# full_motor_1.net
KiCad netlist of a schematic drawn in EAGLE
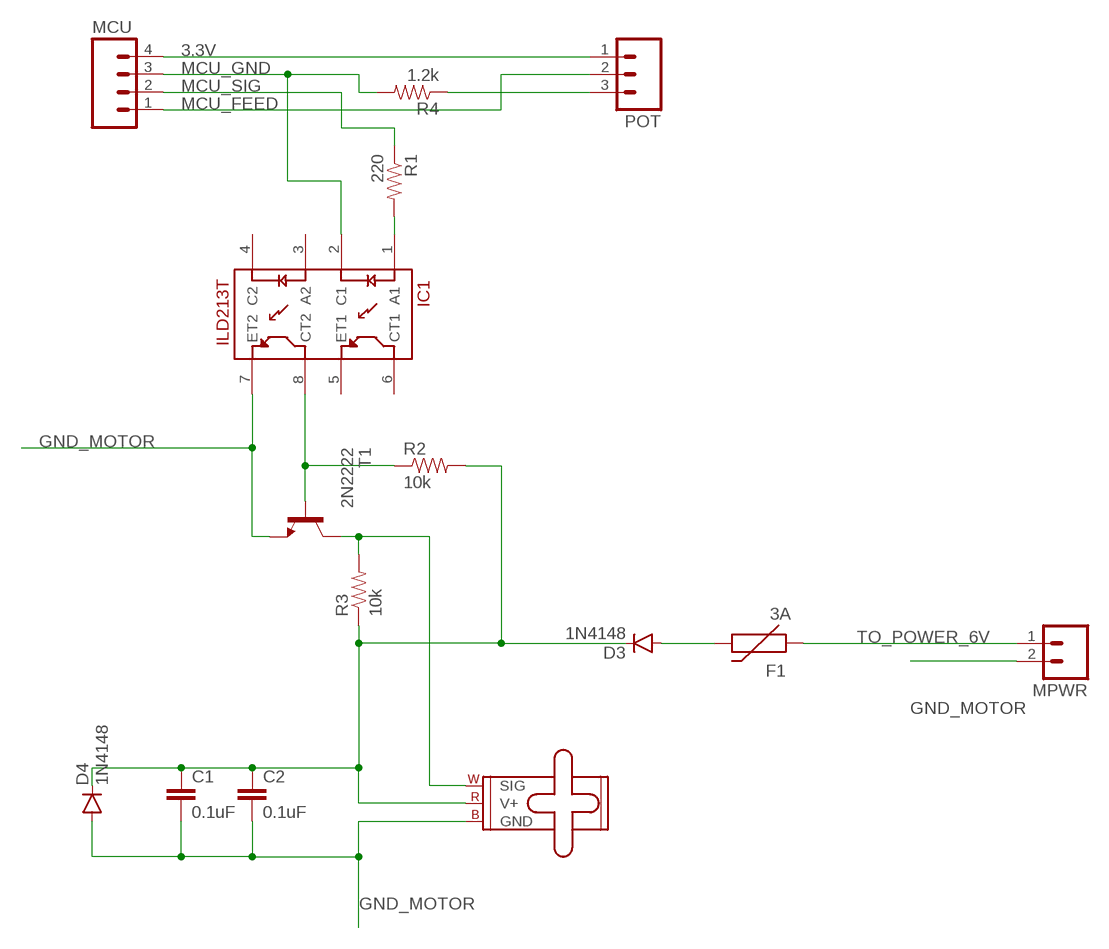
[diagram p0: schematic, sheet 1]

(export (version "E")
  (design (tool "Eeschema 10.0.6"))
  (components
    (comp (ref "C1")
      (value "0.1uF")
      (footprint "eagle-import:1206")
      (libsource (lib "eagle-import") (part "CAP1206"))
    )
    (comp (ref "C2")
      (value "0.1uF")
      (footprint "eagle-import:1206")
      (libsource (lib "eagle-import") (part "CAP1206"))
    )
    (comp (ref "D3")
      (value "1N4148")
      (footprint "eagle-import:DIODE-1N4148")
      (libsource (lib "eagle-import") (part "DIODE1N4148"))
    )
    (comp (ref "D4")
      (value "1N4148")
      (footprint "eagle-import:DIODE-1N4148")
      (libsource (lib "eagle-import") (part "DIODE1N4148"))
    )
    (comp (ref "F1")
      (value "3A")
      (footprint "eagle-import:PTC-1206")
      (libsource (lib "eagle-import") (part "PTCSMD"))
    )
    (comp (ref "IC1")
      (value "ILD213T")
      (footprint "eagle-import:SO08")
      (libsource (lib "eagle-import") (part "ILD213T"))
    )
    (comp (ref "MCU")
      (value "M04PTH")
      (footprint "eagle-import:1X04")
      (libsource (lib "eagle-import") (part "M04PTH"))
    )
    (comp (ref "MPWR")
      (value "M02PTH")
      (footprint "eagle-import:1X02")
      (libsource (lib "eagle-import") (part "M02PTH"))
    )
    (comp (ref "POT")
      (value "M03PTH")
      (footprint "eagle-import:1X03")
      (libsource (lib "eagle-import") (part "M03PTH"))
    )
    (comp (ref "R1")
      (value "220")
      (footprint "eagle-import:1206")
      (libsource (lib "eagle-import") (part "RESISTOR1206"))
    )
    (comp (ref "R2")
      (value "10k")
      (footprint "eagle-import:1206")
      (libsource (lib "eagle-import") (part "RESISTOR1206"))
    )
    (comp (ref "R3")
      (value "10k")
      (footprint "eagle-import:1206")
      (libsource (lib "eagle-import") (part "RESISTOR1206"))
    )
    (comp (ref "R4")
      (value "1.2k")
      (footprint "eagle-import:1206")
      (libsource (lib "eagle-import") (part "RESISTOR1206"))
    )
    (comp (ref "SERVO")
      (value "SMALL_SERVO")
      (footprint "eagle-import:1X03")
      (libsource (lib "eagle-import") (part "SMALL_SERVO"))
    )
    (comp (ref "T1")
      (value "2N2222")
      (footprint "eagle-import:TO92-EBC-OVAL")
      (libsource (lib "eagle-import") (part "2N2222"))
    )
  )
  (nets
    (net (code "1") (name "/3.3V") (class "Default")
      (node (ref "MCU") (pin "4") (pinfunction "4_4") (pintype "passive"))
      (node (ref "POT") (pin "1") (pinfunction "1_1") (pintype "passive"))
    )
    (net (code "2") (name "/GND_MOTOR") (class "Default")
      (node (ref "C1") (pin "2") (pinfunction "2_2") (pintype "passive"))
      (node (ref "C2") (pin "2") (pinfunction "2_2") (pintype "passive"))
      (node (ref "D4") (pin "A") (pinfunction "A_A") (pintype "passive"))
      (node (ref "IC1") (pin "7") (pinfunction "ET2_7") (pintype "bidirectional"))
      (node (ref "MPWR") (pin "2") (pinfunction "2_2") (pintype "passive"))
      (node (ref "SERVO") (pin "3") (pinfunction "GND_3") (pintype "bidirectional"))
      (node (ref "T1") (pin "E") (pinfunction "E_E") (pintype "passive"))
    )
    (net (code "3") (name "/MCU_FEED") (class "Default")
      (node (ref "MCU") (pin "1") (pinfunction "1_1") (pintype "passive"))
      (node (ref "POT") (pin "2") (pinfunction "2_2") (pintype "passive"))
    )
    (net (code "4") (name "/MCU_GND") (class "Default")
      (node (ref "IC1") (pin "2") (pinfunction "C1_2") (pintype "bidirectional"))
      (node (ref "MCU") (pin "3") (pinfunction "3_3") (pintype "passive"))
      (node (ref "R4") (pin "2") (pinfunction "2_2") (pintype "passive"))
    )
    (net (code "5") (name "/MCU_SIG") (class "Default")
      (node (ref "MCU") (pin "2") (pinfunction "2_2") (pintype "passive"))
      (node (ref "R1") (pin "1") (pinfunction "1_1") (pintype "passive"))
    )
    (net (code "6") (name "/TO_POWER_6V") (class "Default")
      (node (ref "F1") (pin "1") (pinfunction "1_1") (pintype "bidirectional"))
      (node (ref "MPWR") (pin "1") (pinfunction "1_1") (pintype "passive"))
    )
    (net (code "7") (name "Net-(D3-PadA)") (class "Default")
      (node (ref "D3") (pin "A") (pinfunction "A_A") (pintype "passive"))
      (node (ref "F1") (pin "2") (pinfunction "2_2") (pintype "bidirectional"))
    )
    (net (code "8") (name "Net-(IC1-A1)") (class "Default")
      (node (ref "IC1") (pin "1") (pinfunction "A1_1") (pintype "bidirectional"))
      (node (ref "R1") (pin "2") (pinfunction "2_2") (pintype "passive"))
    )
    (net (code "9") (name "Net-(IC1-CT2)") (class "Default")
      (node (ref "IC1") (pin "8") (pinfunction "CT2_8") (pintype "bidirectional"))
      (node (ref "R2") (pin "1") (pinfunction "1_1") (pintype "passive"))
      (node (ref "T1") (pin "B") (pinfunction "B_B") (pintype "passive"))
    )
    (net (code "10") (name "Net-(POT-Pad3)") (class "Default")
      (node (ref "POT") (pin "3") (pinfunction "3_3") (pintype "passive"))
      (node (ref "R4") (pin "1") (pinfunction "1_1") (pintype "passive"))
    )
    (net (code "11") (name "Net-(SERVO-SIG)") (class "Default")
      (node (ref "R3") (pin "2") (pinfunction "2_2") (pintype "passive"))
      (node (ref "SERVO") (pin "1") (pinfunction "SIG_1") (pintype "bidirectional"))
      (node (ref "T1") (pin "C") (pinfunction "C_C") (pintype "passive"))
    )
    (net (code "12") (name "Net-(SERVO-V+)") (class "Default")
      (node (ref "C1") (pin "1") (pinfunction "1_1") (pintype "passive"))
      (node (ref "C2") (pin "1") (pinfunction "1_1") (pintype "passive"))
      (node (ref "D3") (pin "C") (pinfunction "C_C") (pintype "passive"))
      (node (ref "D4") (pin "C") (pinfunction "C_C") (pintype "passive"))
      (node (ref "R2") (pin "2") (pinfunction "2_2") (pintype "passive"))
      (node (ref "R3") (pin "1") (pinfunction "1_1") (pintype "passive"))
      (node (ref "SERVO") (pin "2") (pinfunction "V+_2") (pintype "bidirectional"))
    )
    (net (code "13") (name "unconnected-(IC1-A2-Pad3)") (class "Default")
      (node (ref "IC1") (pin "3") (pinfunction "A2_3") (pintype "bidirectional"))
    )
    (net (code "14") (name "unconnected-(IC1-C2-Pad4)") (class "Default")
      (node (ref "IC1") (pin "4") (pinfunction "C2_4") (pintype "bidirectional"))
    )
    (net (code "15") (name "unconnected-(IC1-CT1-Pad6)") (class "Default")
      (node (ref "IC1") (pin "6") (pinfunction "CT1_6") (pintype "bidirectional"))
    )
    (net (code "16") (name "unconnected-(IC1-ET1-Pad5)") (class "Default")
      (node (ref "IC1") (pin "5") (pinfunction "ET1_5") (pintype "bidirectional"))
    )
  )
)
